# Amp2.net
KiCad netlist of a schematic drawn in EasyEDA
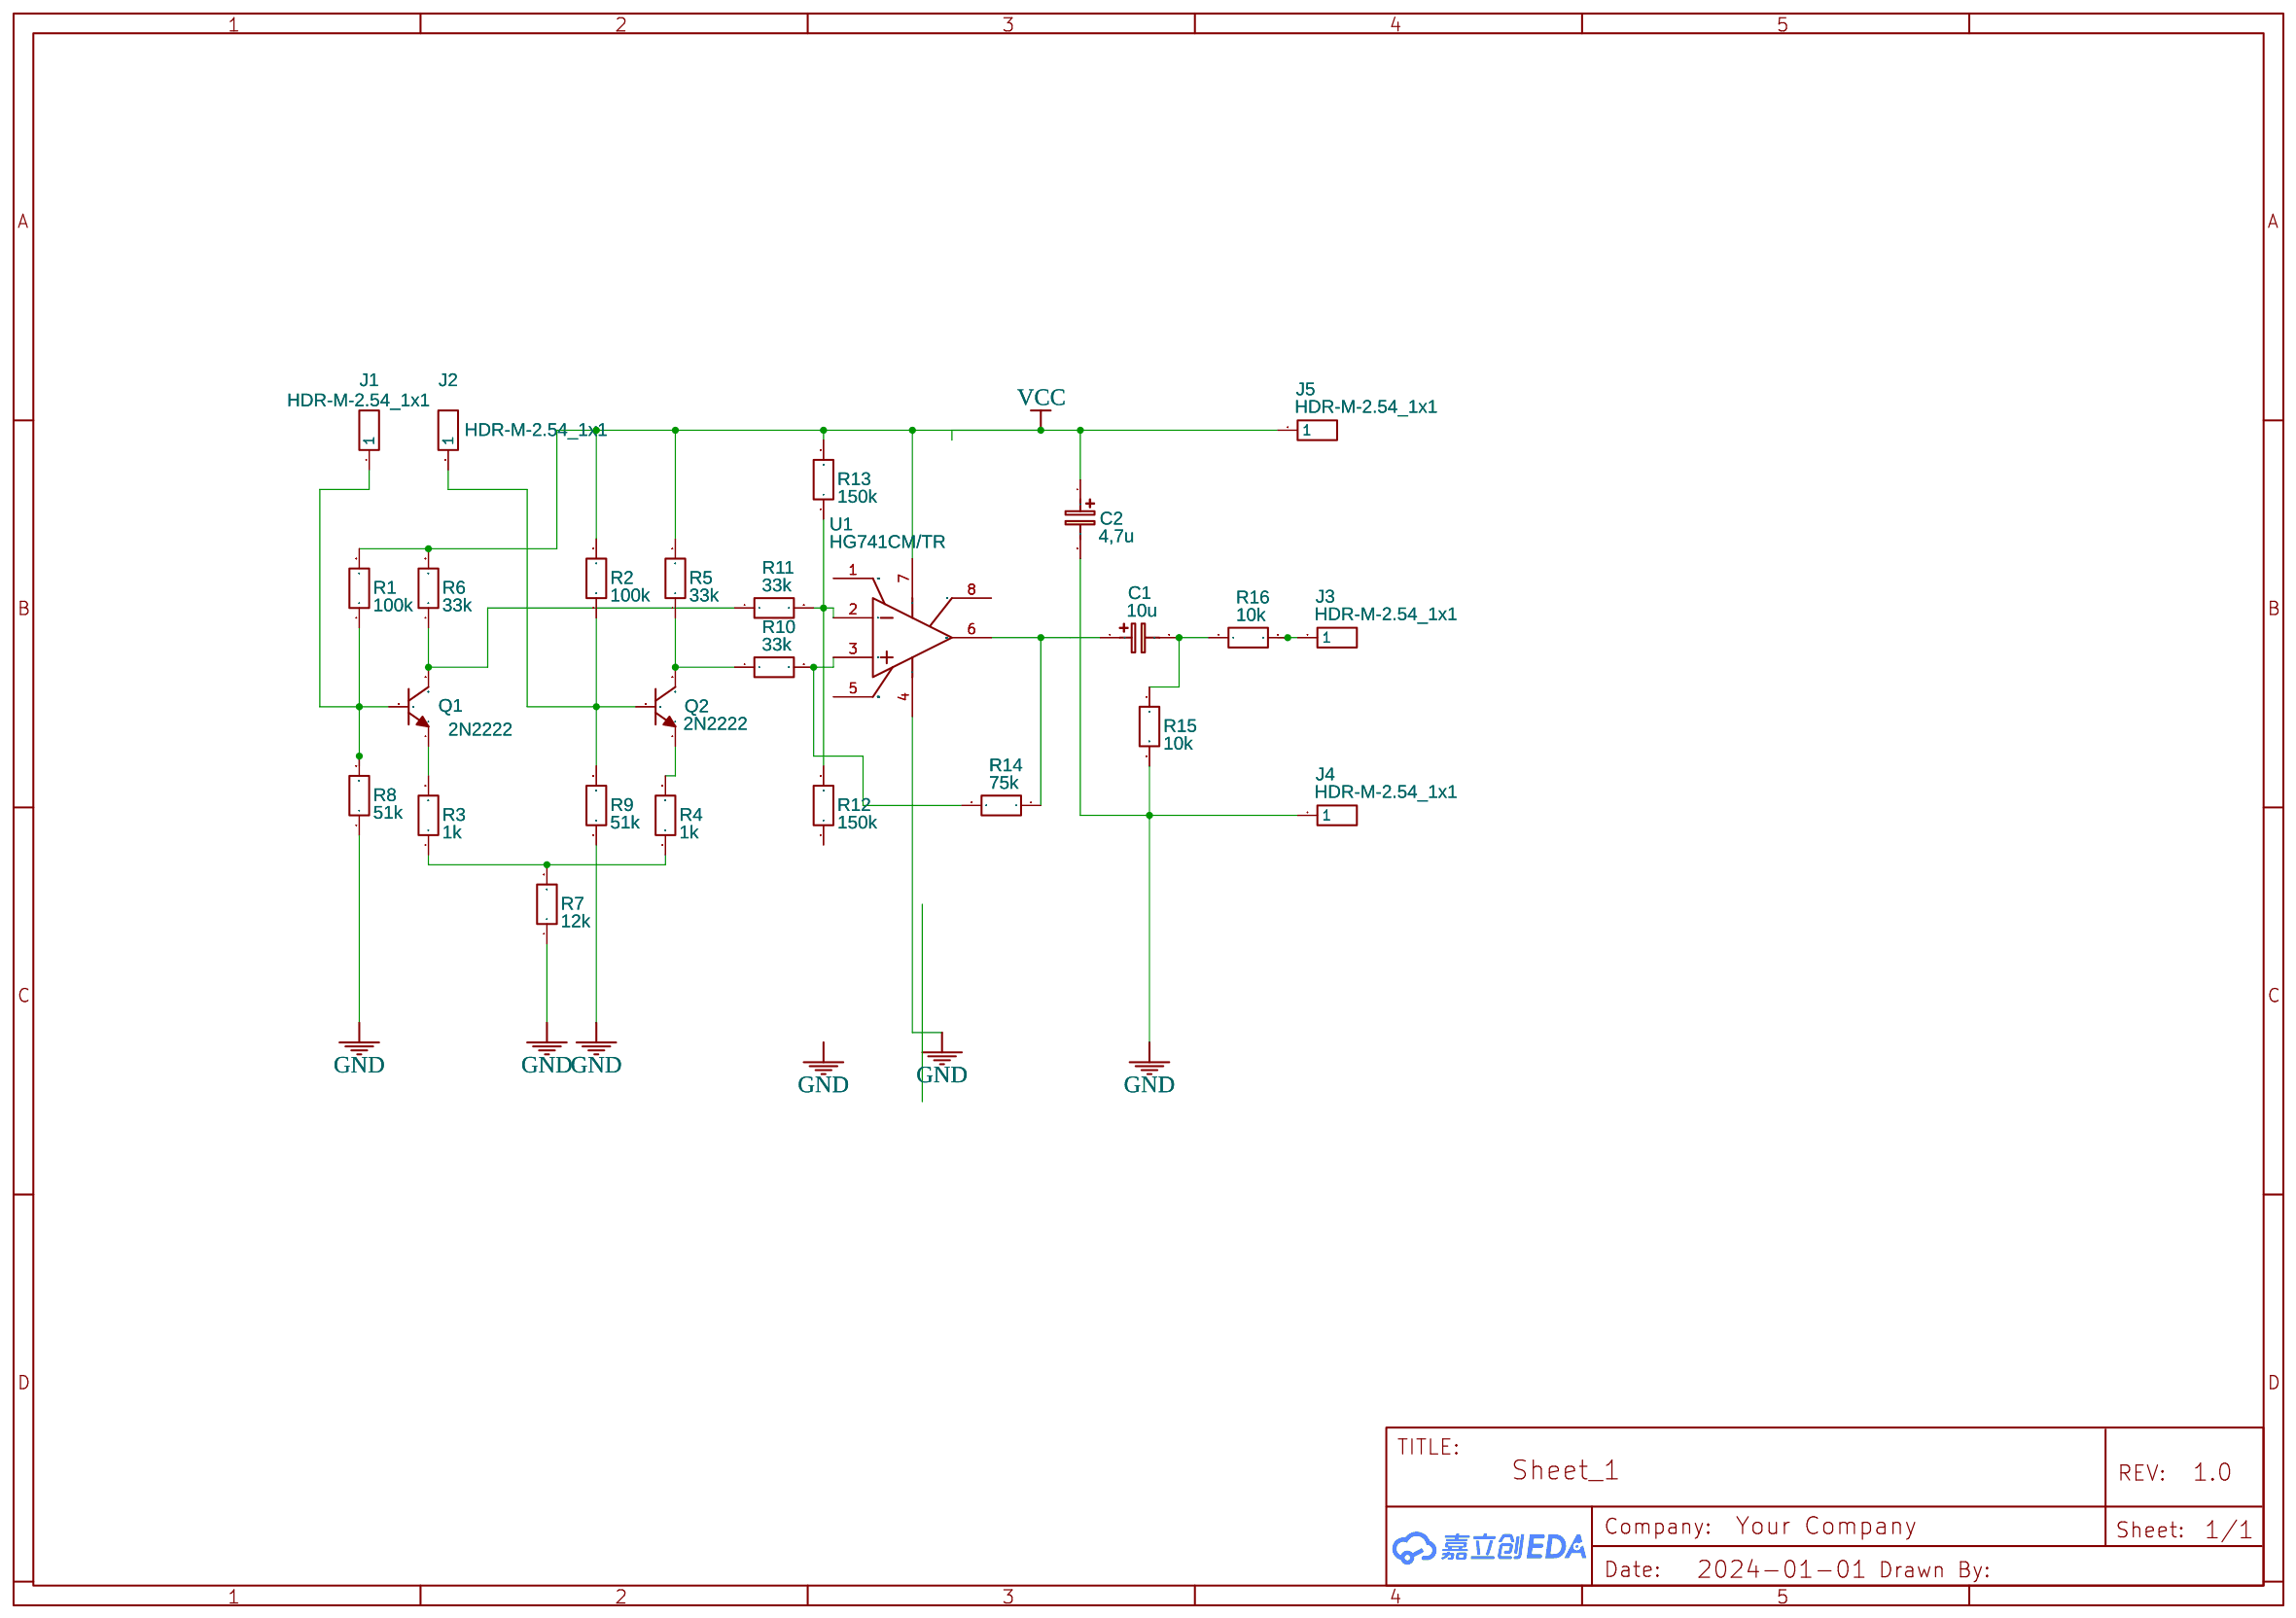
[diagram p0: schematic sheet]

(export (version "E")
  (design (tool "Eeschema 10.0.6"))
  (components
    (comp (ref "C1") (value "10u") (libsource (lib "") (part "C_Tan_SMD_A_EU")))
    (comp (ref "C2") (value "4,7u") (libsource (lib "") (part "C_Tan_SMD_A_EU_1")))
    (comp (ref "J1")
      (value "HDR-M-2.54_1x1")
      (fields (field (name "BOM_Supplier Part") "C81276"))
      (libsource (lib "") (part "HDR-M-2.54_1x1_1"))
    )
    (comp (ref "J2")
      (value "HDR-M-2.54_1x1")
      (fields (field (name "BOM_Supplier Part") "C81276"))
      (libsource (lib "") (part "HDR-M-2.54_1x1_1"))
    )
    (comp (ref "J3")
      (value "HDR-M-2.54_1x1")
      (fields (field (name "BOM_Supplier Part") "C81276"))
      (libsource (lib "") (part "HDR-M-2.54_1x1"))
    )
    (comp (ref "J4")
      (value "HDR-M-2.54_1x1")
      (fields (field (name "BOM_Supplier Part") "C81276"))
      (libsource (lib "") (part "HDR-M-2.54_1x1"))
    )
    (comp (ref "J5")
      (value "HDR-M-2.54_1x1")
      (fields (field (name "BOM_Supplier Part") "C81276"))
      (libsource (lib "") (part "HDR-M-2.54_1x1"))
    )
    (comp (ref "Q1")
      (value "2N2222")
      (fields
        (field (name "BOM_Manufacturer Part") "2n3904S-RTK/PS")
        (field (name "BOM_Supplier Part") "C18536")
      )
      (libsource (lib "") (part "2N3904(SOT-23)"))
    )
    (comp (ref "Q2")
      (value "2N2222")
      (fields
        (field (name "BOM_Manufacturer Part") "2n3904S-RTK/PS")
        (field (name "BOM_Supplier Part") "C18536")
      )
      (libsource (lib "") (part "2N3904(SOT-23)"))
    )
    (comp (ref "R1") (value "100k") (libsource (lib "") (part "R_0603_EU_3")))
    (comp (ref "R2") (value "100k") (libsource (lib "") (part "R_0603_EU_3")))
    (comp (ref "R3") (value "1k") (libsource (lib "") (part "R_0603_EU_3")))
    (comp (ref "R4") (value "1k") (libsource (lib "") (part "R_0603_EU_3")))
    (comp (ref "R5") (value "33k") (libsource (lib "") (part "R_0603_EU_3")))
    (comp (ref "R6") (value "33k") (libsource (lib "") (part "R_0603_EU_3")))
    (comp (ref "R7") (value "12k") (libsource (lib "") (part "R_0603_EU_3")))
    (comp (ref "R8") (value "51k") (libsource (lib "") (part "R_0603_EU_3")))
    (comp (ref "R9") (value "51k") (libsource (lib "") (part "R_0603_EU_3")))
    (comp (ref "R10") (value "33k") (libsource (lib "") (part "R_0603_EU")))
    (comp (ref "R11") (value "33k") (libsource (lib "") (part "R_0603_EU")))
    (comp (ref "R12") (value "150k") (libsource (lib "") (part "R_0603_EU_3")))
    (comp (ref "R13") (value "150k") (libsource (lib "") (part "R_0603_EU_3")))
    (comp (ref "R14") (value "75k") (libsource (lib "") (part "R_0603_EU_1")))
    (comp (ref "R15") (value "10k") (libsource (lib "") (part "R_0603_EU_2")))
    (comp (ref "R16") (value "10k") (libsource (lib "") (part "R_0603_EU")))
    (comp (ref "U1")
      (value "HG741CM/TR")
      (fields (field (name "Manufacturer") "HGSEMI(华冠)"))
      (libsource (lib "") (part "HG741CM/TR"))
    )
  )
  (nets
    (net (code "1") (name "GND") (class "Default")
      (node (ref "C2") (pin "2") (pinfunction "2_2") (pintype "unspecified"))
      (node (ref "J4") (pin "1") (pinfunction "1_1") (pintype "input"))
      (node (ref "R15") (pin "2") (pinfunction "2_2") (pintype "unspecified"))
      (node (ref "R7") (pin "1") (pinfunction "1_1") (pintype "unspecified"))
      (node (ref "R8") (pin "1") (pinfunction "1_1") (pintype "unspecified"))
      (node (ref "R9") (pin "1") (pinfunction "1_1") (pintype "unspecified"))
      (node (ref "U1") (pin "4") (pinfunction "V-_4") (pintype "passive"))
    )
    (net (code "2") (name "Net-(C1-Pad2)") (class "Default")
      (node (ref "C1") (pin "2") (pinfunction "2_2") (pintype "unspecified"))
      (node (ref "R15") (pin "1") (pinfunction "1_1") (pintype "unspecified"))
      (node (ref "R16") (pin "1") (pinfunction "1_1") (pintype "unspecified"))
    )
    (net (code "3") (name "Net-(J3-Pad1)") (class "Default")
      (node (ref "J3") (pin "1") (pinfunction "1_1") (pintype "input"))
      (node (ref "R16") (pin "2") (pinfunction "2_2") (pintype "unspecified"))
    )
    (net (code "4") (name "Net-(Q1-B)") (class "Default")
      (node (ref "J1") (pin "1") (pinfunction "1_1") (pintype "input"))
      (node (ref "Q1") (pin "2") (pinfunction "B_2") (pintype "input"))
      (node (ref "R1") (pin "1") (pinfunction "1_1") (pintype "unspecified"))
      (node (ref "R8") (pin "2") (pinfunction "2_2") (pintype "unspecified"))
    )
    (net (code "5") (name "Net-(Q1-C)") (class "Default")
      (node (ref "Q1") (pin "3") (pinfunction "C_3") (pintype "input"))
      (node (ref "R11") (pin "1") (pinfunction "1_1") (pintype "unspecified"))
      (node (ref "R6") (pin "1") (pinfunction "1_1") (pintype "unspecified"))
    )
    (net (code "6") (name "Net-(Q1-E)") (class "Default")
      (node (ref "Q1") (pin "1") (pinfunction "E_1") (pintype "input"))
      (node (ref "R3") (pin "2") (pinfunction "2_2") (pintype "unspecified"))
    )
    (net (code "7") (name "Net-(Q2-B)") (class "Default")
      (node (ref "J2") (pin "1") (pinfunction "1_1") (pintype "input"))
      (node (ref "Q2") (pin "2") (pinfunction "B_2") (pintype "input"))
      (node (ref "R2") (pin "1") (pinfunction "1_1") (pintype "unspecified"))
      (node (ref "R9") (pin "2") (pinfunction "2_2") (pintype "unspecified"))
    )
    (net (code "8") (name "Net-(Q2-C)") (class "Default")
      (node (ref "Q2") (pin "3") (pinfunction "C_3") (pintype "input"))
      (node (ref "R10") (pin "1") (pinfunction "1_1") (pintype "unspecified"))
      (node (ref "R5") (pin "1") (pinfunction "1_1") (pintype "unspecified"))
    )
    (net (code "9") (name "Net-(Q2-E)") (class "Default")
      (node (ref "Q2") (pin "1") (pinfunction "E_1") (pintype "input"))
      (node (ref "R4") (pin "2") (pinfunction "2_2") (pintype "unspecified"))
    )
    (net (code "10") (name "Net-(R3-Pad1)") (class "Default")
      (node (ref "R3") (pin "1") (pinfunction "1_1") (pintype "unspecified"))
      (node (ref "R4") (pin "1") (pinfunction "1_1") (pintype "unspecified"))
      (node (ref "R7") (pin "2") (pinfunction "2_2") (pintype "unspecified"))
    )
    (net (code "11") (name "Net-(U1-+IN)") (class "Default")
      (node (ref "R10") (pin "2") (pinfunction "2_2") (pintype "unspecified"))
      (node (ref "R14") (pin "2") (pinfunction "2_2") (pintype "unspecified"))
      (node (ref "U1") (pin "3") (pinfunction "+IN_3") (pintype "unspecified"))
    )
    (net (code "12") (name "Net-(U1--IN)") (class "Default")
      (node (ref "R11") (pin "2") (pinfunction "2_2") (pintype "unspecified"))
      (node (ref "R12") (pin "2") (pinfunction "2_2") (pintype "unspecified"))
      (node (ref "R13") (pin "1") (pinfunction "1_1") (pintype "unspecified"))
      (node (ref "U1") (pin "2") (pinfunction "-IN_2") (pintype "unspecified"))
    )
    (net (code "13") (name "Net-(U1-OUTPUT)") (class "Default")
      (node (ref "C1") (pin "1") (pinfunction "1_1") (pintype "unspecified"))
      (node (ref "R14") (pin "1") (pinfunction "1_1") (pintype "unspecified"))
      (node (ref "U1") (pin "6") (pinfunction "OUTPUT_6") (pintype "unspecified"))
    )
    (net (code "14") (name "VCC") (class "Default")
      (node (ref "C2") (pin "1") (pinfunction "1_1") (pintype "unspecified"))
      (node (ref "J5") (pin "1") (pinfunction "1_1") (pintype "input"))
      (node (ref "R1") (pin "2") (pinfunction "2_2") (pintype "unspecified"))
      (node (ref "R13") (pin "2") (pinfunction "2_2") (pintype "unspecified"))
      (node (ref "R2") (pin "2") (pinfunction "2_2") (pintype "unspecified"))
      (node (ref "R5") (pin "2") (pinfunction "2_2") (pintype "unspecified"))
      (node (ref "R6") (pin "2") (pinfunction "2_2") (pintype "unspecified"))
      (node (ref "U1") (pin "7") (pinfunction "V+_7") (pintype "passive"))
    )
    (net (code "15") (name "unconnected-(R12-Pad1)") (class "Default")
      (node (ref "R12") (pin "1") (pinfunction "1_1") (pintype "unspecified"))
    )
    (net (code "16") (name "unconnected-(U1-NC-Pad8)") (class "Default")
      (node (ref "U1") (pin "8") (pinfunction "NC_8") (pintype "unspecified"))
    )
    (net (code "17") (name "unconnected-(U1-OFFSET_NULL-Pad1)") (class "Default")
      (node (ref "U1") (pin "1") (pinfunction "OFFSET_NULL_1") (pintype "unspecified"))
    )
    (net (code "18") (name "unconnected-(U1-OFFSET_NULL-Pad5)") (class "Default")
      (node (ref "U1") (pin "5") (pinfunction "OFFSET_NULL_5") (pintype "unspecified"))
    )
  )
)
